# rftoy1_1.net
KiCad netlist of a schematic drawn in EAGLE
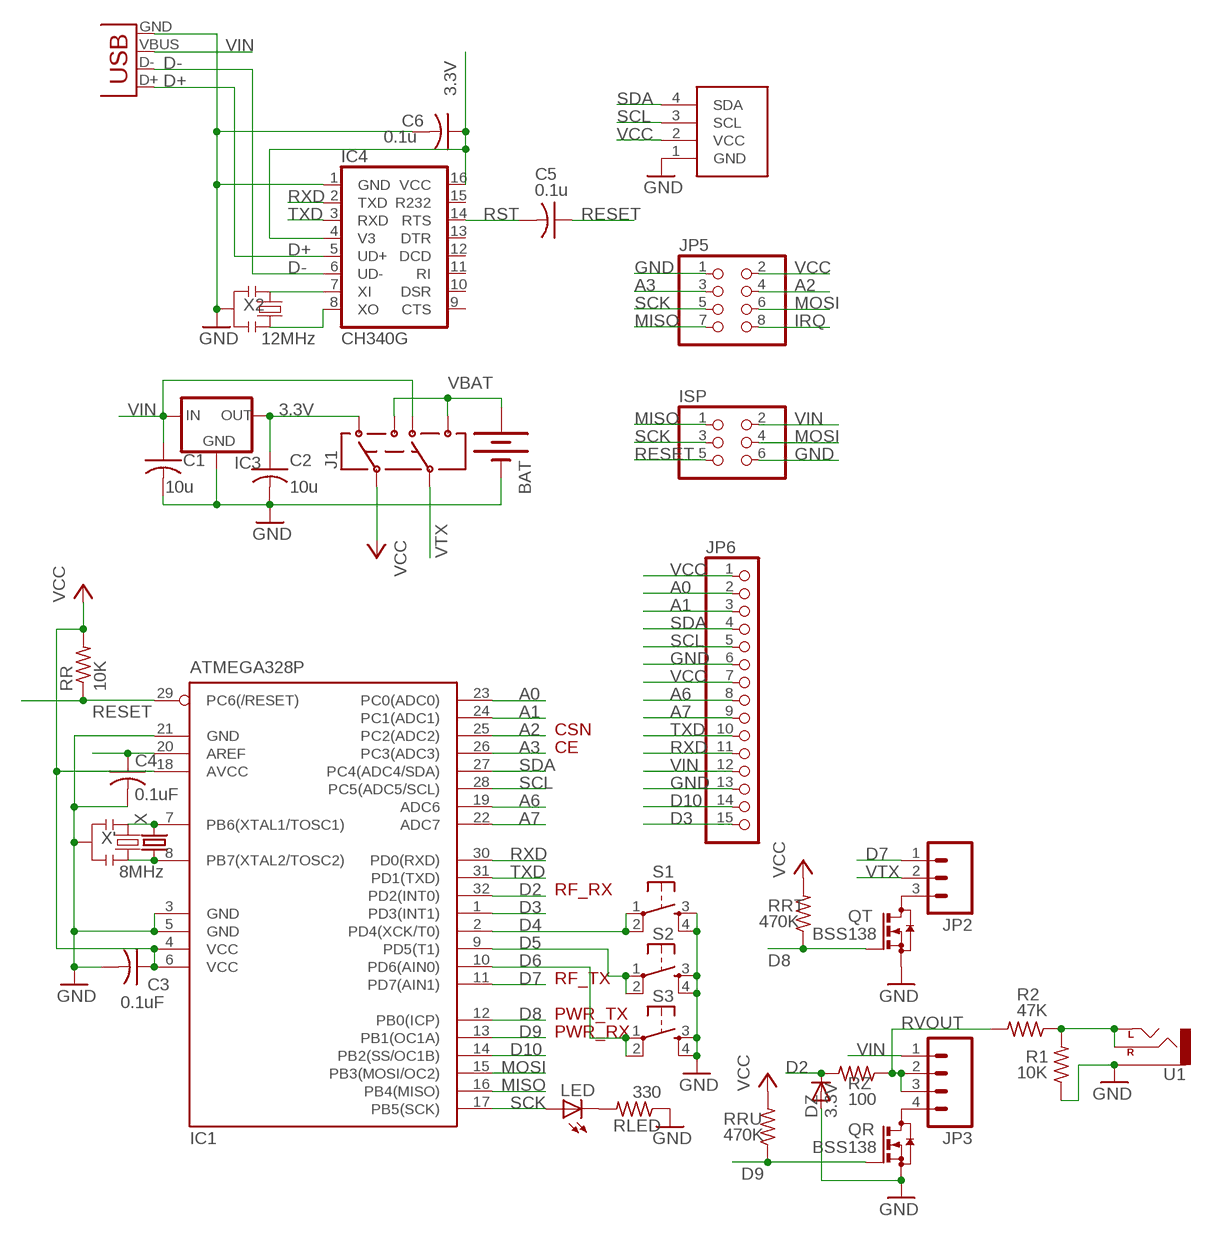
[diagram p0: schematic, sheet 1]

(export (version "E")
  (design (tool "Eeschema 10.0.6"))
  (components
    (comp (ref "BAT")
      (value "BATTERY20PTH")
      (footprint "eagle-import:BATTCOM_20MM_PTH")
      (libsource (lib "eagle-import") (part "BATTERY20PTH"))
    )
    (comp (ref "C1")
      (value "10u")
      (footprint "eagle-import:C0805K")
      (libsource (lib "eagle-import") (part "adafruit2013_C-USC0805K"))
    )
    (comp (ref "C2")
      (value "10u")
      (footprint "eagle-import:C0805K")
      (libsource (lib "eagle-import") (part "adafruit2013_C-USC0805K"))
    )
    (comp (ref "C3")
      (value "0.1uF")
      (footprint "eagle-import:C0603K")
      (libsource (lib "eagle-import") (part "adafruit2013_C-USC0603K"))
    )
    (comp (ref "C4")
      (value "0.1uF")
      (footprint "eagle-import:C0603K")
      (libsource (lib "eagle-import") (part "adafruit2013_C-USC0603K"))
    )
    (comp (ref "C5")
      (value "0.1u")
      (footprint "eagle-import:C0603K")
      (libsource (lib "eagle-import") (part "C-USC0603K"))
    )
    (comp (ref "C6")
      (value "0.1u")
      (footprint "eagle-import:C0603K")
      (libsource (lib "eagle-import") (part "C-USC0603K"))
    )
    (comp (ref "DZ")
      (value "3.3V")
      (footprint "eagle-import:MINIMELF")
      (libsource (lib "eagle-import") (part "DIODE-MINIMELF"))
    )
    (comp (ref "IC1")
      (value "ATMEGA328P")
      (footprint "eagle-import:TQFP32-08")
      (fields (field (name "MPN") "ATMEGA8-16AU"))
      (libsource (lib "eagle-import") (part "MEGA8-AI"))
    )
    (comp (ref "IC3")
      (value "MCP1700SOT233")
      (footprint "eagle-import:SOT23")
      (libsource (lib "eagle-import") (part "MCP1700SOT233"))
    )
    (comp (ref "IC4")
      (value "CH340G")
      (footprint "eagle-import:SO16")
      (libsource (lib "eagle-import") (part "CH340G"))
    )
    (comp (ref "ISP")
      (value "PINHD-2X3")
      (footprint "eagle-import:2X03")
      (libsource (lib "eagle-import") (part "PINHD-2X3"))
    )
    (comp (ref "J1")
      (value "AYZ0202")
      (footprint "eagle-import:AYZ0202")
      (libsource (lib "eagle-import") (part "AYZ0202"))
    )
    (comp (ref "JP2")
      (value "M03LOCK_LONGPADS")
      (footprint "eagle-import:1X03_LOCK_LONGPADS")
      (libsource (lib "eagle-import") (part "M03LOCK_LONGPADS"))
    )
    (comp (ref "JP3")
      (value "M04LOCK")
      (footprint "eagle-import:1X04_LOCK")
      (libsource (lib "eagle-import") (part "M04LOCK"))
    )
    (comp (ref "JP5")
      (value "PINHD-2X4")
      (footprint "eagle-import:2X04")
      (libsource (lib "eagle-import") (part "PINHD-2X4"))
    )
    (comp (ref "JP6")
      (value "PINHD-1X15-CB")
      (footprint "eagle-import:1X15-CB")
      (libsource (lib "eagle-import") (part "PINHD-1X15-CB"))
    )
    (comp (ref "LED")
      (value "LEDCHIPLED_0805")
      (footprint "eagle-import:CHIPLED_0805")
      (libsource (lib "eagle-import") (part "LEDCHIPLED_0805"))
    )
    (comp (ref "QR")
      (value "BSS138")
      (footprint "eagle-import:SOT23")
      (libsource (lib "eagle-import") (part "BSS123"))
    )
    (comp (ref "QT")
      (value "BSS138")
      (footprint "eagle-import:SOT23")
      (libsource (lib "eagle-import") (part "BSS123"))
    )
    (comp (ref "R1")
      (value "10K")
      (footprint "eagle-import:R0805")
      (libsource (lib "eagle-import") (part "R-US_R0805"))
    )
    (comp (ref "R2")
      (value "47K")
      (footprint "eagle-import:R0805")
      (libsource (lib "eagle-import") (part "R-US_R0805"))
    )
    (comp (ref "RLED")
      (value "330")
      (footprint "eagle-import:R0805")
      (libsource (lib "eagle-import") (part "R-US_R0805"))
    )
    (comp (ref "RR")
      (value "10K")
      (footprint "eagle-import:R0805")
      (libsource (lib "eagle-import") (part "R-US_R0805"))
    )
    (comp (ref "RRT")
      (value "470K")
      (footprint "eagle-import:R0805")
      (libsource (lib "eagle-import") (part "R-US_R0805"))
    )
    (comp (ref "RRU")
      (value "470K")
      (footprint "eagle-import:R0805")
      (libsource (lib "eagle-import") (part "R-US_R0805"))
    )
    (comp (ref "RZ")
      (value "100")
      (footprint "eagle-import:R0805")
      (libsource (lib "eagle-import") (part "R-US_R0805"))
    )
    (comp (ref "S1")
      (value "TAC_SWITCHPTH")
      (footprint "eagle-import:TACTILE-PTH")
      (libsource (lib "eagle-import") (part "TAC_SWITCHPTH"))
    )
    (comp (ref "S2")
      (value "TAC_SWITCHPTH")
      (footprint "eagle-import:TACTILE-PTH")
      (libsource (lib "eagle-import") (part "TAC_SWITCHPTH"))
    )
    (comp (ref "S3")
      (value "TAC_SWITCHPTH")
      (footprint "eagle-import:TACTILE-PTH")
      (libsource (lib "eagle-import") (part "TAC_SWITCHPTH"))
    )
    (comp (ref "U$1")
      (value "SSD1306_OLED_I2C")
      (footprint "eagle-import:SSD1306_OLED_I2C")
      (libsource (lib "eagle-import") (part "SSD1306_OLED_I2C"))
    )
    (comp (ref "U1")
      (value "AUDIO-JACKSMD3")
      (footprint "eagle-import:AUDIO-JACK-3.5MM-SMD3")
      (libsource (lib "eagle-import") (part "AUDIO-JACKSMD3"))
    )
    (comp (ref "X")
      (value "CRYSTALTC26V")
      (footprint "eagle-import:TC26V")
      (libsource (lib "eagle-import") (part "CRYSTALTC26V"))
    )
    (comp (ref "X'")
      (value "8MHz")
      (footprint "eagle-import:RESONATOR-SMD")
      (libsource (lib "eagle-import") (part "RESONATORSMD"))
    )
    (comp (ref "X1")
      (value "USBSMD")
      (footprint "eagle-import:USB-MINIB")
      (libsource (lib "eagle-import") (part "USBSMD"))
    )
    (comp (ref "X2")
      (value "12MHz")
      (footprint "eagle-import:RESONATOR-SMD")
      (libsource (lib "eagle-import") (part "RESONATORSMD"))
    )
  )
  (nets
    (net (code "1") (name "/3.3V") (class "Default")
      (node (ref "C2") (pin "1") (pinfunction "1_1") (pintype "passive"))
      (node (ref "C6") (pin "1") (pinfunction "1_1") (pintype "passive"))
      (node (ref "IC3") (pin "2") (pinfunction "OUT_2") (pintype "passive"))
      (node (ref "IC4") (pin "16") (pinfunction "VCC_16") (pintype "power_in"))
      (node (ref "IC4") (pin "4") (pinfunction "V3_4") (pintype "bidirectional"))
      (node (ref "J1") (pin "3") (pinfunction "1_3") (pintype "bidirectional"))
    )
    (net (code "2") (name "/A0") (class "Default")
      (node (ref "IC1") (pin "23") (pinfunction "PC0(ADC0)_23") (pintype "bidirectional"))
      (node (ref "JP6") (pin "2") (pinfunction "2_2") (pintype "passive"))
    )
    (net (code "3") (name "/A1") (class "Default")
      (node (ref "IC1") (pin "24") (pinfunction "PC1(ADC1)_24") (pintype "bidirectional"))
      (node (ref "JP6") (pin "3") (pinfunction "3_3") (pintype "passive"))
    )
    (net (code "4") (name "/A2") (class "Default")
      (node (ref "IC1") (pin "25") (pinfunction "PC2(ADC2)_25") (pintype "bidirectional"))
      (node (ref "JP5") (pin "4") (pinfunction "4_4") (pintype "passive"))
    )
    (net (code "5") (name "/A3") (class "Default")
      (node (ref "IC1") (pin "26") (pinfunction "PC3(ADC3)_26") (pintype "bidirectional"))
      (node (ref "JP5") (pin "3") (pinfunction "3_3") (pintype "passive"))
    )
    (net (code "6") (name "/A6") (class "Default")
      (node (ref "IC1") (pin "19") (pinfunction "ADC6_19") (pintype "bidirectional"))
      (node (ref "JP6") (pin "8") (pinfunction "8_8") (pintype "passive"))
    )
    (net (code "7") (name "/A7") (class "Default")
      (node (ref "IC1") (pin "22") (pinfunction "ADC7_22") (pintype "bidirectional"))
      (node (ref "JP6") (pin "9") (pinfunction "9_9") (pintype "passive"))
    )
    (net (code "8") (name "/D+") (class "Default")
      (node (ref "IC4") (pin "5") (pinfunction "UD+_5") (pintype "bidirectional"))
      (node (ref "X1") (pin "D+") (pinfunction "D+_D+") (pintype "bidirectional"))
    )
    (net (code "9") (name "/D-") (class "Default")
      (node (ref "IC4") (pin "6") (pinfunction "UD-_6") (pintype "bidirectional"))
      (node (ref "X1") (pin "D-") (pinfunction "D-_D-") (pintype "bidirectional"))
    )
    (net (code "10") (name "/D2") (class "Default")
      (node (ref "DZ") (pin "C") (pinfunction "C_C") (pintype "passive"))
      (node (ref "IC1") (pin "32") (pinfunction "PD2(INT0)_32") (pintype "bidirectional"))
      (node (ref "RZ") (pin "2") (pinfunction "2_2") (pintype "passive"))
    )
    (net (code "11") (name "/D3") (class "Default")
      (node (ref "IC1") (pin "1") (pinfunction "PD3(INT1)_1") (pintype "bidirectional"))
      (node (ref "JP6") (pin "15") (pinfunction "15_15") (pintype "passive"))
    )
    (net (code "12") (name "/D4") (class "Default")
      (node (ref "IC1") (pin "2") (pinfunction "PD4(XCK/T0)_2") (pintype "bidirectional"))
      (node (ref "S1") (pin "1") (pinfunction "1_1") (pintype "passive"))
      (node (ref "S1") (pin "2") (pinfunction "2_2") (pintype "passive"))
    )
    (net (code "13") (name "/D5") (class "Default")
      (node (ref "IC1") (pin "9") (pinfunction "PD5(T1)_9") (pintype "bidirectional"))
      (node (ref "S2") (pin "1") (pinfunction "1_1") (pintype "passive"))
      (node (ref "S2") (pin "2") (pinfunction "2_2") (pintype "passive"))
    )
    (net (code "14") (name "/D6") (class "Default")
      (node (ref "IC1") (pin "10") (pinfunction "PD6(AIN0)_10") (pintype "bidirectional"))
      (node (ref "S3") (pin "1") (pinfunction "1_1") (pintype "passive"))
      (node (ref "S3") (pin "2") (pinfunction "2_2") (pintype "passive"))
    )
    (net (code "15") (name "/D7") (class "Default")
      (node (ref "IC1") (pin "11") (pinfunction "PD7(AIN1)_11") (pintype "bidirectional"))
      (node (ref "JP2") (pin "1") (pinfunction "1_1") (pintype "passive"))
    )
    (net (code "16") (name "/D8") (class "Default")
      (node (ref "IC1") (pin "12") (pinfunction "PB0(ICP)_12") (pintype "bidirectional"))
      (node (ref "QT") (pin "1") (pinfunction "G_1") (pintype "passive"))
      (node (ref "RRT") (pin "1") (pinfunction "1_1") (pintype "passive"))
    )
    (net (code "17") (name "/D9") (class "Default")
      (node (ref "IC1") (pin "13") (pinfunction "PB1(OC1A)_13") (pintype "bidirectional"))
      (node (ref "QR") (pin "1") (pinfunction "G_1") (pintype "passive"))
      (node (ref "RRU") (pin "1") (pinfunction "1_1") (pintype "passive"))
    )
    (net (code "18") (name "/D10") (class "Default")
      (node (ref "IC1") (pin "14") (pinfunction "PB2(SS/OC1B)_14") (pintype "bidirectional"))
      (node (ref "JP6") (pin "14") (pinfunction "14_14") (pintype "passive"))
    )
    (net (code "19") (name "/IRQ") (class "Default")
      (node (ref "JP5") (pin "8") (pinfunction "8_8") (pintype "passive"))
    )
    (net (code "20") (name "/MISO") (class "Default")
      (node (ref "IC1") (pin "16") (pinfunction "PB4(MISO)_16") (pintype "bidirectional"))
      (node (ref "ISP") (pin "1") (pinfunction "1_1") (pintype "passive"))
      (node (ref "JP5") (pin "7") (pinfunction "7_7") (pintype "passive"))
    )
    (net (code "21") (name "/MOSI") (class "Default")
      (node (ref "IC1") (pin "15") (pinfunction "PB3(MOSI/OC2)_15") (pintype "bidirectional"))
      (node (ref "ISP") (pin "4") (pinfunction "4_4") (pintype "passive"))
      (node (ref "JP5") (pin "6") (pinfunction "6_6") (pintype "passive"))
    )
    (net (code "22") (name "/RESET") (class "Default")
      (node (ref "C5") (pin "1") (pinfunction "1_1") (pintype "passive"))
      (node (ref "IC1") (pin "29") (pinfunction "PC6(/RESET)_29") (pintype "bidirectional"))
      (node (ref "ISP") (pin "5") (pinfunction "5_5") (pintype "passive"))
      (node (ref "RR") (pin "1") (pinfunction "1_1") (pintype "passive"))
    )
    (net (code "23") (name "/RST") (class "Default")
      (node (ref "C5") (pin "2") (pinfunction "2_2") (pintype "passive"))
      (node (ref "IC4") (pin "14") (pinfunction "RTS_14") (pintype "bidirectional"))
    )
    (net (code "24") (name "/RVOUT") (class "Default")
      (node (ref "JP3") (pin "2") (pinfunction "2_2") (pintype "passive"))
      (node (ref "JP3") (pin "3") (pinfunction "3_3") (pintype "passive"))
      (node (ref "R2") (pin "2") (pinfunction "2_2") (pintype "passive"))
      (node (ref "RZ") (pin "1") (pinfunction "1_1") (pintype "passive"))
    )
    (net (code "25") (name "/RXD") (class "Default")
      (node (ref "IC1") (pin "30") (pinfunction "PD0(RXD)_30") (pintype "bidirectional"))
      (node (ref "IC4") (pin "2") (pinfunction "TXD_2") (pintype "bidirectional"))
      (node (ref "JP6") (pin "11") (pinfunction "11_11") (pintype "passive"))
    )
    (net (code "26") (name "/SCK") (class "Default")
      (node (ref "IC1") (pin "17") (pinfunction "PB5(SCK)_17") (pintype "bidirectional"))
      (node (ref "ISP") (pin "3") (pinfunction "3_3") (pintype "passive"))
      (node (ref "JP5") (pin "5") (pinfunction "5_5") (pintype "passive"))
      (node (ref "LED") (pin "A") (pinfunction "A_A") (pintype "passive"))
    )
    (net (code "27") (name "/SCL") (class "Default")
      (node (ref "IC1") (pin "28") (pinfunction "PC5(ADC5/SCL)_28") (pintype "bidirectional"))
      (node (ref "JP6") (pin "5") (pinfunction "5_5") (pintype "passive"))
      (node (ref "U$1") (pin "3") (pinfunction "SCL_3") (pintype "bidirectional"))
    )
    (net (code "28") (name "/SDA") (class "Default")
      (node (ref "IC1") (pin "27") (pinfunction "PC4(ADC4/SDA)_27") (pintype "bidirectional"))
      (node (ref "JP6") (pin "4") (pinfunction "4_4") (pintype "passive"))
      (node (ref "U$1") (pin "4") (pinfunction "SDA_4") (pintype "bidirectional"))
    )
    (net (code "29") (name "/TXD") (class "Default")
      (node (ref "IC1") (pin "31") (pinfunction "PD1(TXD)_31") (pintype "bidirectional"))
      (node (ref "IC4") (pin "3") (pinfunction "RXD_3") (pintype "bidirectional"))
      (node (ref "JP6") (pin "10") (pinfunction "10_10") (pintype "passive"))
    )
    (net (code "30") (name "/VBAT") (class "Default")
      (node (ref "BAT") (pin "1") (pinfunction "+_1") (pintype "power_in"))
      (node (ref "J1") (pin "1") (pinfunction "3_1") (pintype "bidirectional"))
      (node (ref "J1") (pin "4") (pinfunction "6_4") (pintype "bidirectional"))
    )
    (net (code "31") (name "/VIN") (class "Default")
      (node (ref "C1") (pin "1") (pinfunction "1_1") (pintype "passive"))
      (node (ref "IC3") (pin "3") (pinfunction "IN_3") (pintype "input"))
      (node (ref "ISP") (pin "2") (pinfunction "2_2") (pintype "passive"))
      (node (ref "J1") (pin "6") (pinfunction "4_6") (pintype "bidirectional"))
      (node (ref "JP3") (pin "1") (pinfunction "1_1") (pintype "passive"))
      (node (ref "JP6") (pin "12") (pinfunction "12_12") (pintype "passive"))
      (node (ref "X1") (pin "VBUS") (pinfunction "VBUS_VBUS") (pintype "bidirectional"))
    )
    (net (code "32") (name "/VTX") (class "Default")
      (node (ref "J1") (pin "5") (pinfunction "5_5") (pintype "bidirectional"))
      (node (ref "JP2") (pin "2") (pinfunction "2_2") (pintype "passive"))
    )
    (net (code "33") (name "GND") (class "Default")
      (node (ref "BAT") (pin "2") (pinfunction "-_2") (pintype "power_in"))
      (node (ref "C1") (pin "2") (pinfunction "2_2") (pintype "passive"))
      (node (ref "C2") (pin "2") (pinfunction "2_2") (pintype "passive"))
      (node (ref "C3") (pin "2") (pinfunction "2_2") (pintype "passive"))
      (node (ref "C4") (pin "2") (pinfunction "2_2") (pintype "passive"))
      (node (ref "C6") (pin "2") (pinfunction "2_2") (pintype "passive"))
      (node (ref "DZ") (pin "A") (pinfunction "A_A") (pintype "passive"))
      (node (ref "IC1") (pin "21") (pinfunction "GND_21") (pintype "power_in"))
      (node (ref "IC1") (pin "3") (pinfunction "GND_3") (pintype "power_in"))
      (node (ref "IC1") (pin "5") (pinfunction "GND_5") (pintype "power_in"))
      (node (ref "IC3") (pin "1") (pinfunction "GND_1") (pintype "input"))
      (node (ref "IC4") (pin "1") (pinfunction "GND_1") (pintype "power_in"))
      (node (ref "ISP") (pin "6") (pinfunction "6_6") (pintype "passive"))
      (node (ref "JP5") (pin "1") (pinfunction "1_1") (pintype "passive"))
      (node (ref "JP6") (pin "13") (pinfunction "13_13") (pintype "passive"))
      (node (ref "JP6") (pin "6") (pinfunction "6_6") (pintype "passive"))
      (node (ref "QR") (pin "2") (pinfunction "S_2") (pintype "passive"))
      (node (ref "QT") (pin "2") (pinfunction "S_2") (pintype "passive"))
      (node (ref "R1") (pin "1") (pinfunction "1_1") (pintype "passive"))
      (node (ref "RLED") (pin "1") (pinfunction "1_1") (pintype "passive"))
      (node (ref "S1") (pin "3") (pinfunction "3_3") (pintype "passive"))
      (node (ref "S1") (pin "4") (pinfunction "4_4") (pintype "passive"))
      (node (ref "S2") (pin "3") (pinfunction "3_3") (pintype "passive"))
      (node (ref "S2") (pin "4") (pinfunction "4_4") (pintype "passive"))
      (node (ref "S3") (pin "3") (pinfunction "3_3") (pintype "passive"))
      (node (ref "S3") (pin "4") (pinfunction "4_4") (pintype "passive"))
      (node (ref "U$1") (pin "1") (pinfunction "GND_1") (pintype "power_in"))
      (node (ref "U1") (pin "RING") (pinfunction "SLEEVE_RING") (pintype "bidirectional"))
      (node (ref "X'") (pin "2") (pinfunction "2_2") (pintype "passive"))
      (node (ref "X1") (pin "GND") (pinfunction "GND_GND") (pintype "bidirectional"))
      (node (ref "X2") (pin "2") (pinfunction "2_2") (pintype "passive"))
    )
    (net (code "34") (name "Net-(IC1-AREF)") (class "Default")
      (node (ref "C4") (pin "1") (pinfunction "1_1") (pintype "passive"))
      (node (ref "IC1") (pin "20") (pinfunction "AREF_20") (pintype "passive"))
    )
    (net (code "35") (name "Net-(IC1-PB6(XTAL1{slash}TOSC1))") (class "Default")
      (node (ref "IC1") (pin "7") (pinfunction "PB6(XTAL1/TOSC1)_7") (pintype "bidirectional"))
      (node (ref "X") (pin "2") (pinfunction "2_2") (pintype "passive"))
      (node (ref "X'") (pin "1") (pinfunction "1_1") (pintype "passive"))
    )
    (net (code "36") (name "Net-(IC1-PB7(XTAL2{slash}TOSC2))") (class "Default")
      (node (ref "IC1") (pin "8") (pinfunction "PB7(XTAL2/TOSC2)_8") (pintype "bidirectional"))
      (node (ref "X") (pin "1") (pinfunction "1_1") (pintype "passive"))
      (node (ref "X'") (pin "3") (pinfunction "3_3") (pintype "passive"))
    )
    (net (code "37") (name "Net-(IC4-XI)") (class "Default")
      (node (ref "IC4") (pin "7") (pinfunction "XI_7") (pintype "bidirectional"))
      (node (ref "X2") (pin "1") (pinfunction "1_1") (pintype "passive"))
    )
    (net (code "38") (name "Net-(IC4-XO)") (class "Default")
      (node (ref "IC4") (pin "8") (pinfunction "XO_8") (pintype "bidirectional"))
      (node (ref "X2") (pin "3") (pinfunction "3_3") (pintype "passive"))
    )
    (net (code "39") (name "Net-(LED-PadC)") (class "Default")
      (node (ref "LED") (pin "C") (pinfunction "C_C") (pintype "passive"))
      (node (ref "RLED") (pin "2") (pinfunction "2_2") (pintype "passive"))
    )
    (net (code "40") (name "Net-(QR-D)") (class "Default")
      (node (ref "JP3") (pin "4") (pinfunction "4_4") (pintype "passive"))
      (node (ref "QR") (pin "3") (pinfunction "D_3") (pintype "passive"))
    )
    (net (code "41") (name "Net-(QT-D)") (class "Default")
      (node (ref "JP2") (pin "3") (pinfunction "3_3") (pintype "passive"))
      (node (ref "QT") (pin "3") (pinfunction "D_3") (pintype "passive"))
    )
    (net (code "42") (name "Net-(U1-LEFT)") (class "Default")
      (node (ref "R1") (pin "2") (pinfunction "2_2") (pintype "passive"))
      (node (ref "R2") (pin "1") (pinfunction "1_1") (pintype "passive"))
      (node (ref "U1") (pin "MID") (pinfunction "RIGHT_MID") (pintype "bidirectional"))
      (node (ref "U1") (pin "TIP") (pinfunction "LEFT_TIP") (pintype "bidirectional"))
    )
    (net (code "43") (name "VCC") (class "Default")
      (node (ref "C3") (pin "1") (pinfunction "1_1") (pintype "passive"))
      (node (ref "IC1") (pin "18") (pinfunction "AVCC_18") (pintype "power_in"))
      (node (ref "IC1") (pin "4") (pinfunction "VCC_4") (pintype "power_in"))
      (node (ref "IC1") (pin "6") (pinfunction "VCC_6") (pintype "power_in"))
      (node (ref "J1") (pin "2") (pinfunction "2_2") (pintype "bidirectional"))
      (node (ref "JP5") (pin "2") (pinfunction "2_2") (pintype "passive"))
      (node (ref "JP6") (pin "1") (pinfunction "1_1") (pintype "passive"))
      (node (ref "JP6") (pin "7") (pinfunction "7_7") (pintype "passive"))
      (node (ref "RR") (pin "2") (pinfunction "2_2") (pintype "passive"))
      (node (ref "RRT") (pin "2") (pinfunction "2_2") (pintype "passive"))
      (node (ref "RRU") (pin "2") (pinfunction "2_2") (pintype "passive"))
      (node (ref "U$1") (pin "2") (pinfunction "VCC_2") (pintype "power_in"))
    )
    (net (code "44") (name "unconnected-(IC4-CTS-Pad9)") (class "Default")
      (node (ref "IC4") (pin "9") (pinfunction "CTS_9") (pintype "bidirectional"))
    )
    (net (code "45") (name "unconnected-(IC4-DCD-Pad12)") (class "Default")
      (node (ref "IC4") (pin "12") (pinfunction "DCD_12") (pintype "bidirectional"))
    )
    (net (code "46") (name "unconnected-(IC4-DSR-Pad10)") (class "Default")
      (node (ref "IC4") (pin "10") (pinfunction "DSR_10") (pintype "bidirectional"))
    )
    (net (code "47") (name "unconnected-(IC4-DTR-Pad13)") (class "Default")
      (node (ref "IC4") (pin "13") (pinfunction "DTR_13") (pintype "bidirectional"))
    )
    (net (code "48") (name "unconnected-(IC4-R232-Pad15)") (class "Default")
      (node (ref "IC4") (pin "15") (pinfunction "R232_15") (pintype "bidirectional"))
    )
    (net (code "49") (name "unconnected-(IC4-RI-Pad11)") (class "Default")
      (node (ref "IC4") (pin "11") (pinfunction "RI_11") (pintype "bidirectional"))
    )
  )
)
